# design.net
KiCad netlist of a schematic drawn in Altium Designer
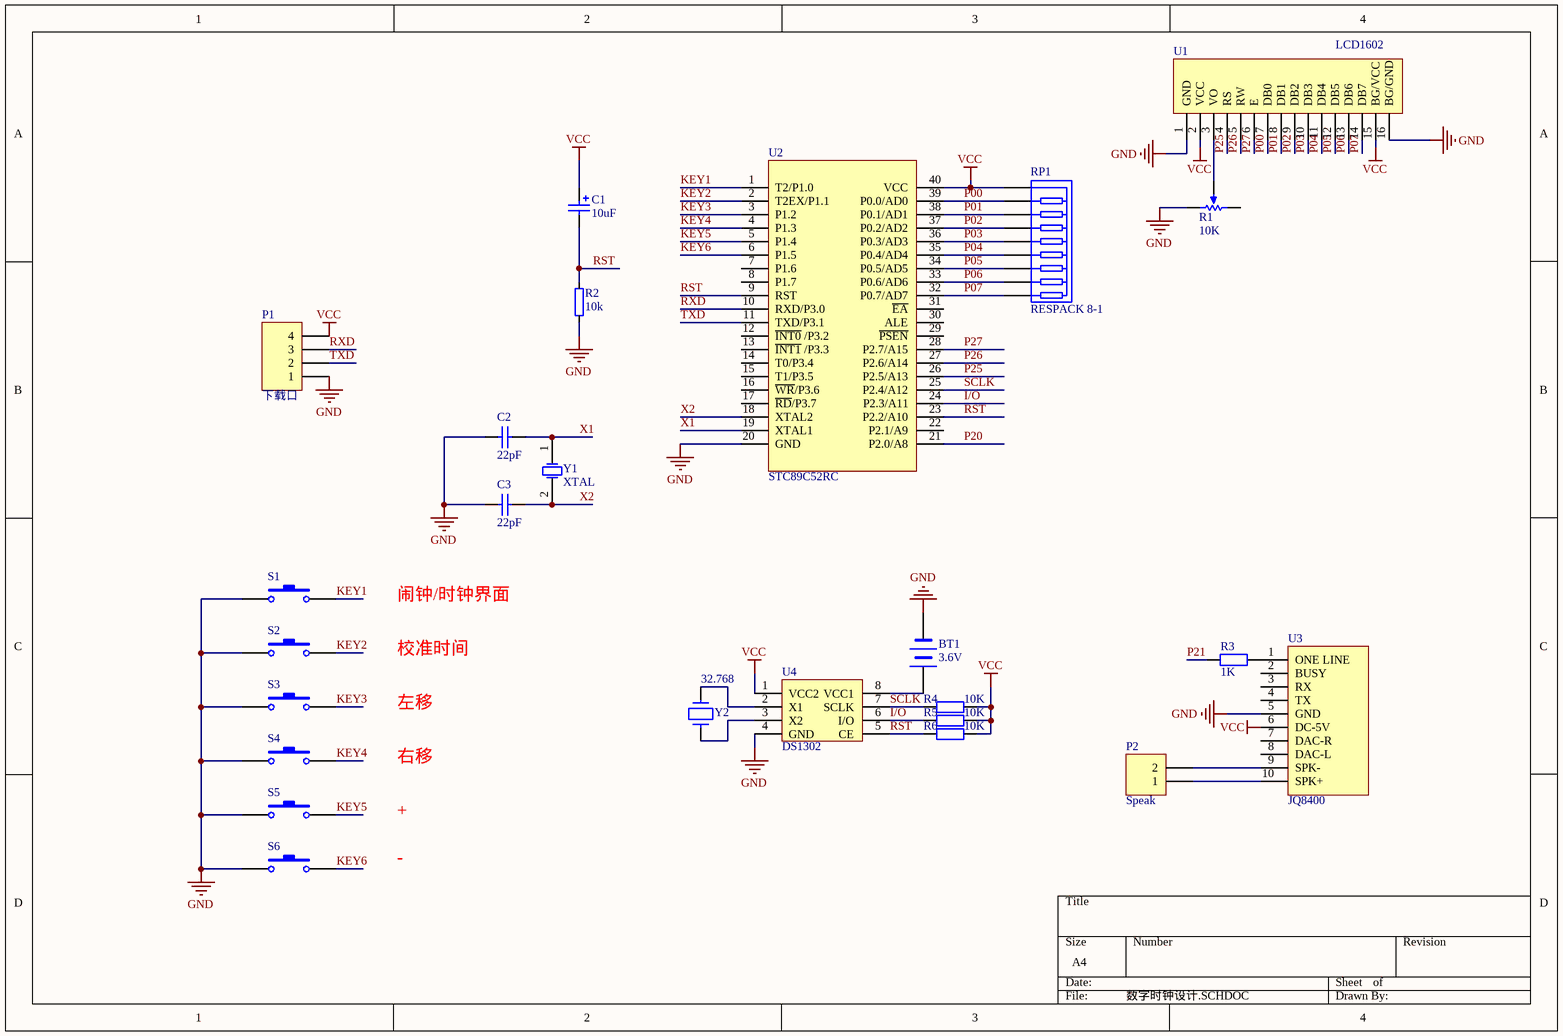
[diagram p0: 数字时钟设计.SCHDOC]

(export (version "E")
  (design (tool "Eeschema 10.0.6"))
  (components
    (comp (ref "BT1")
      (value "3.6V")
      (footprint "BT1220")
      (description "Battery")
      (libsource (lib "常用1") (part "BATTERY"))
    )
    (comp (ref "C1")
      (value "10uF")
      (footprint "1206C+")
      (description "Polarized Capacitor (Axial)")
      (fields (field (name "PUBLISHER") "Altium Limited"))
      (libsource (lib "Miscellaneous Devices") (part "Cap Pol2"))
    )
    (comp (ref "C2")
      (value "22pF")
      (footprint "0805")
      (description "Capacitor")
      (fields (field (name "Comment") "Cap") (field (name "PUBLISHER") "Altium Limited"))
      (libsource (lib "Miscellaneous Devices") (part "Cap"))
    )
    (comp (ref "C3")
      (value "22pF")
      (footprint "0805")
      (description "Capacitor")
      (fields (field (name "Comment") "Cap") (field (name "PUBLISHER") "Altium Limited"))
      (libsource (lib "Miscellaneous Devices") (part "Cap"))
    )
    (comp (ref "P1")
      (value "下载口")
      (footprint "HDR1X4")
      (description "Header, 4-Pin")
      (fields (field (name "PUBLISHER") "Altium Limited"))
      (libsource (lib "Miscellaneous Connectors") (part "Header 4"))
    )
    (comp (ref "P2")
      (value "Speak")
      (footprint "HDR1X2")
      (description "Header, 2-Pin")
      (fields (field (name "PUBLISHER") "Altium Limited"))
      (libsource (lib "Miscellaneous Connectors") (part "Header 2"))
    )
    (comp (ref "R1")
      (value "10K")
      (footprint "VR5")
      (description "Potentiometer")
      (fields (field (name "Comment") "RPot") (field (name "PUBLISHER") "Altium Limited"))
      (libsource (lib "Miscellaneous Devices") (part "RPot"))
    )
    (comp (ref "R2") (value "10k") (footprint "0805") (libsource (lib "SCHS") (part "RES5")))
    (comp (ref "R3")
      (value "1K")
      (footprint "AXIAL-0.4")
      (description "Resistor")
      (fields (field (name "Comment") "Res2") (field (name "PUBLISHER") "Altium Limited"))
      (libsource (lib "Miscellaneous Devices") (part "Res2"))
    )
    (comp (ref "R4")
      (value "10K")
      (footprint "0603r")
      (description "Resistor")
      (fields (field (name "PUBLISHER") "Altium Limited"))
      (libsource (lib "Miscellaneous Devices") (part "Res2"))
    )
    (comp (ref "R5")
      (value "10K")
      (footprint "0603r")
      (description "Resistor")
      (fields (field (name "PUBLISHER") "Altium Limited"))
      (libsource (lib "Miscellaneous Devices") (part "Res2"))
    )
    (comp (ref "R6")
      (value "10K")
      (footprint "0603r")
      (description "Resistor")
      (fields (field (name "PUBLISHER") "Altium Limited"))
      (libsource (lib "Miscellaneous Devices") (part "Res2"))
    )
    (comp (ref "RP1") (value "RESPACK 8-1") (footprint "SIP9") (libsource (lib "符号") (part "RESPACK 8-1")))
    (comp (ref "S1")
      (value "~")
      (footprint "KEY")
      (description "Switch")
      (fields (field (name "PUBLISHER") "Altium Limited"))
      (libsource (lib "Miscellaneous Devices") (part "SW-PB"))
    )
    (comp (ref "S2")
      (value "~")
      (footprint "KEY")
      (description "Switch")
      (fields (field (name "PUBLISHER") "Altium Limited"))
      (libsource (lib "Miscellaneous Devices") (part "SW-PB"))
    )
    (comp (ref "S3")
      (value "~")
      (footprint "KEY")
      (description "Switch")
      (fields (field (name "PUBLISHER") "Altium Limited"))
      (libsource (lib "Miscellaneous Devices") (part "SW-PB"))
    )
    (comp (ref "S4")
      (value "~")
      (footprint "KEY")
      (description "Switch")
      (fields (field (name "PUBLISHER") "Altium Limited"))
      (libsource (lib "Miscellaneous Devices") (part "SW-PB"))
    )
    (comp (ref "S5")
      (value "~")
      (footprint "KEY")
      (description "Switch")
      (fields (field (name "PUBLISHER") "Altium Limited"))
      (libsource (lib "Miscellaneous Devices") (part "SW-PB"))
    )
    (comp (ref "S6")
      (value "~")
      (footprint "KEY")
      (description "Switch")
      (fields (field (name "PUBLISHER") "Altium Limited"))
      (libsource (lib "Miscellaneous Devices") (part "SW-PB"))
    )
    (comp (ref "U1") (value "LCD1602") (footprint "HDR1X16") (libsource (lib "个人") (part "LCD1602")))
    (comp (ref "U2") (value "STC89C52RC") (footprint "DIP40") (libsource (lib "SCHS") (part "STC89C52RC")))
    (comp (ref "U3") (value "JQ8400") (libsource (lib "Schlib1") (part "JQ8400")))
    (comp (ref "U4") (value "DS1302") (libsource (lib "个人") (part "DS1302")))
    (comp (ref "Y1")
      (value "XTAL")
      (footprint "XTAL")
      (description "Crystal Oscillator")
      (fields (field (name "PUBLISHER") "Altium Limited"))
      (libsource (lib "Miscellaneous Devices") (part "XTAL"))
    )
    (comp (ref "Y2") (value "32.768") (footprint "XTAL_2x6") (libsource (lib "常用元件库") (part "CRYSTAL")))
  )
  (nets
    (net (code "1") (name "/I{slash}O") (class "Default")
      (node (ref "R5") (pin "1") (pinfunction "1_1") (pintype "passive"))
      (node (ref "U2") (pin "24") (pinfunction "P2.3/A11_24") (pintype "passive"))
      (node (ref "U4") (pin "6") (pinfunction "I/O_6") (pintype "passive"))
    )
    (net (code "2") (name "/KEY1") (class "Default")
      (node (ref "S1") (pin "2") (pinfunction "2_2") (pintype "passive"))
      (node (ref "U2") (pin "1") (pinfunction "T2/P1.0_1") (pintype "passive"))
    )
    (net (code "3") (name "/KEY2") (class "Default")
      (node (ref "S2") (pin "2") (pinfunction "2_2") (pintype "passive"))
      (node (ref "U2") (pin "2") (pinfunction "T2EX/P1.1_2") (pintype "passive"))
    )
    (net (code "4") (name "/KEY3") (class "Default")
      (node (ref "S3") (pin "2") (pinfunction "2_2") (pintype "passive"))
      (node (ref "U2") (pin "3") (pinfunction "P1.2_3") (pintype "passive"))
    )
    (net (code "5") (name "/KEY4") (class "Default")
      (node (ref "S4") (pin "2") (pinfunction "2_2") (pintype "passive"))
      (node (ref "U2") (pin "4") (pinfunction "P1.3_4") (pintype "passive"))
    )
    (net (code "6") (name "/KEY5") (class "Default")
      (node (ref "S5") (pin "2") (pinfunction "2_2") (pintype "passive"))
      (node (ref "U2") (pin "5") (pinfunction "P1.4_5") (pintype "passive"))
    )
    (net (code "7") (name "/KEY6") (class "Default")
      (node (ref "S6") (pin "2") (pinfunction "2_2") (pintype "passive"))
      (node (ref "U2") (pin "6") (pinfunction "P1.5_6") (pintype "passive"))
    )
    (net (code "8") (name "/P00") (class "Default")
      (node (ref "RP1") (pin "2") (pinfunction "2_2") (pintype "passive"))
      (node (ref "U1") (pin "7") (pinfunction "DB0_7") (pintype "passive"))
      (node (ref "U2") (pin "39") (pinfunction "P0.0/AD0_39") (pintype "passive"))
    )
    (net (code "9") (name "/P01") (class "Default")
      (node (ref "RP1") (pin "3") (pinfunction "3_3") (pintype "passive"))
      (node (ref "U1") (pin "8") (pinfunction "DB1_8") (pintype "passive"))
      (node (ref "U2") (pin "38") (pinfunction "P0.1/AD1_38") (pintype "passive"))
    )
    (net (code "10") (name "/P02") (class "Default")
      (node (ref "RP1") (pin "4") (pinfunction "4_4") (pintype "passive"))
      (node (ref "U1") (pin "9") (pinfunction "DB2_9") (pintype "passive"))
      (node (ref "U2") (pin "37") (pinfunction "P0.2/AD2_37") (pintype "passive"))
    )
    (net (code "11") (name "/P03") (class "Default")
      (node (ref "RP1") (pin "5") (pinfunction "5_5") (pintype "passive"))
      (node (ref "U1") (pin "10") (pinfunction "DB3_10") (pintype "passive"))
      (node (ref "U2") (pin "36") (pinfunction "P0.3/AD3_36") (pintype "passive"))
    )
    (net (code "12") (name "/P04") (class "Default")
      (node (ref "RP1") (pin "6") (pinfunction "6_6") (pintype "passive"))
      (node (ref "U1") (pin "11") (pinfunction "DB4_11") (pintype "passive"))
      (node (ref "U2") (pin "35") (pinfunction "P0.4/AD4_35") (pintype "passive"))
    )
    (net (code "13") (name "/P05") (class "Default")
      (node (ref "RP1") (pin "7") (pinfunction "7_7") (pintype "passive"))
      (node (ref "U1") (pin "12") (pinfunction "DB5_12") (pintype "passive"))
      (node (ref "U2") (pin "34") (pinfunction "P0.5/AD5_34") (pintype "passive"))
    )
    (net (code "14") (name "/P06") (class "Default")
      (node (ref "RP1") (pin "8") (pinfunction "8_8") (pintype "passive"))
      (node (ref "U1") (pin "13") (pinfunction "DB6_13") (pintype "passive"))
      (node (ref "U2") (pin "33") (pinfunction "P0.6/AD6_33") (pintype "passive"))
    )
    (net (code "15") (name "/P07") (class "Default")
      (node (ref "RP1") (pin "9") (pinfunction "9_9") (pintype "passive"))
      (node (ref "U1") (pin "14") (pinfunction "DB7_14") (pintype "passive"))
      (node (ref "U2") (pin "32") (pinfunction "P0.7/AD7_32") (pintype "passive"))
    )
    (net (code "16") (name "/P20") (class "Default")
      (node (ref "U2") (pin "21") (pinfunction "P2.0/A8_21") (pintype "passive"))
    )
    (net (code "17") (name "/P21") (class "Default")
      (node (ref "R3") (pin "1") (pinfunction "1_1") (pintype "passive"))
    )
    (net (code "18") (name "/P25") (class "Default")
      (node (ref "U1") (pin "4") (pinfunction "RS_4") (pintype "passive"))
      (node (ref "U2") (pin "26") (pinfunction "P2.5/A13_26") (pintype "passive"))
    )
    (net (code "19") (name "/P26") (class "Default")
      (node (ref "U1") (pin "5") (pinfunction "RW_5") (pintype "passive"))
      (node (ref "U2") (pin "27") (pinfunction "P2.6/A14_27") (pintype "passive"))
    )
    (net (code "20") (name "/P27") (class "Default")
      (node (ref "U1") (pin "6") (pinfunction "E_6") (pintype "passive"))
      (node (ref "U2") (pin "28") (pinfunction "P2.7/A15_28") (pintype "passive"))
    )
    (net (code "21") (name "/RST") (class "Default")
      (node (ref "C1") (pin "2") (pinfunction "2_2") (pintype "passive"))
      (node (ref "R2") (pin "2") (pintype "passive"))
      (node (ref "R6") (pin "1") (pinfunction "1_1") (pintype "passive"))
      (node (ref "U2") (pin "23") (pinfunction "P2.2/A10_23") (pintype "passive"))
      (node (ref "U2") (pin "9") (pinfunction "RST_9") (pintype "passive"))
      (node (ref "U4") (pin "5") (pinfunction "CE_5") (pintype "passive"))
    )
    (net (code "22") (name "/RXD") (class "Default")
      (node (ref "P1") (pin "3") (pinfunction "3_3") (pintype "passive"))
      (node (ref "U2") (pin "10") (pinfunction "RXD/P3.0_10") (pintype "passive"))
    )
    (net (code "23") (name "/SCLK") (class "Default")
      (node (ref "R4") (pin "1") (pinfunction "1_1") (pintype "passive"))
      (node (ref "U2") (pin "25") (pinfunction "P2.4/A12_25") (pintype "passive"))
      (node (ref "U4") (pin "7") (pinfunction "SCLK_7") (pintype "passive"))
    )
    (net (code "24") (name "/TXD") (class "Default")
      (node (ref "P1") (pin "2") (pinfunction "2_2") (pintype "passive"))
      (node (ref "U2") (pin "11") (pinfunction "TXD/P3.1_11") (pintype "passive"))
    )
    (net (code "25") (name "/X1") (class "Default")
      (node (ref "C2") (pin "2") (pinfunction "2_2") (pintype "passive"))
      (node (ref "U2") (pin "19") (pinfunction "XTAL1_19") (pintype "passive"))
      (node (ref "Y1") (pin "1") (pinfunction "OSC1_1") (pintype "passive"))
    )
    (net (code "26") (name "/X2") (class "Default")
      (node (ref "C3") (pin "2") (pinfunction "2_2") (pintype "passive"))
      (node (ref "U2") (pin "18") (pinfunction "XTAL2_18") (pintype "passive"))
      (node (ref "Y1") (pin "2") (pinfunction "OSC2_2") (pintype "passive"))
    )
    (net (code "27") (name "GND") (class "Default")
      (node (ref "BT1") (pin "2") (pinfunction "-_2") (pintype "passive"))
      (node (ref "C2") (pin "1") (pinfunction "1_1") (pintype "passive"))
      (node (ref "C3") (pin "1") (pinfunction "1_1") (pintype "passive"))
      (node (ref "P1") (pin "1") (pinfunction "1_1") (pintype "passive"))
      (node (ref "R1") (pin "2") (pinfunction "BOT_2") (pintype "passive"))
      (node (ref "R2") (pin "1") (pintype "passive"))
      (node (ref "S1") (pin "1") (pinfunction "1_1") (pintype "passive"))
      (node (ref "S2") (pin "1") (pinfunction "1_1") (pintype "passive"))
      (node (ref "S3") (pin "1") (pinfunction "1_1") (pintype "passive"))
      (node (ref "S4") (pin "1") (pinfunction "1_1") (pintype "passive"))
      (node (ref "S5") (pin "1") (pinfunction "1_1") (pintype "passive"))
      (node (ref "S6") (pin "1") (pinfunction "1_1") (pintype "passive"))
      (node (ref "U1") (pin "1") (pinfunction "GND_1") (pintype "passive"))
      (node (ref "U1") (pin "16") (pinfunction "BG/GND_16") (pintype "passive"))
      (node (ref "U2") (pin "20") (pinfunction "GND_20") (pintype "passive"))
      (node (ref "U3") (pin "5") (pinfunction "GND_5") (pintype "passive"))
      (node (ref "U4") (pin "4") (pinfunction "GND_4") (pintype "passive"))
    )
    (net (code "28") (name "Net-(BT1-+)") (class "Default")
      (node (ref "BT1") (pin "1") (pinfunction "+_1") (pintype "passive"))
      (node (ref "U4") (pin "8") (pinfunction "VCC1_8") (pintype "passive"))
    )
    (net (code "29") (name "Net-(R1-TAP)") (class "Default")
      (node (ref "R1") (pin "3") (pinfunction "TAP_3") (pintype "passive"))
      (node (ref "U1") (pin "3") (pinfunction "VO_3") (pintype "passive"))
    )
    (net (code "30") (name "Net-(U3-ONE_LINE)") (class "Default")
      (node (ref "R3") (pin "2") (pinfunction "2_2") (pintype "passive"))
      (node (ref "U3") (pin "1") (pinfunction "ONE_LINE_1") (pintype "passive"))
    )
    (net (code "31") (name "Net-(U3-SPK+)") (class "Default")
      (node (ref "P2") (pin "1") (pinfunction "1_1") (pintype "passive"))
      (node (ref "U3") (pin "10") (pinfunction "SPK+_10") (pintype "passive"))
    )
    (net (code "32") (name "Net-(U3-SPK-)") (class "Default")
      (node (ref "P2") (pin "2") (pinfunction "2_2") (pintype "passive"))
      (node (ref "U3") (pin "9") (pinfunction "SPK-_9") (pintype "passive"))
    )
    (net (code "33") (name "Net-(U4-X1)") (class "Default")
      (node (ref "U4") (pin "2") (pinfunction "X1_2") (pintype "passive"))
      (node (ref "Y2") (pin "2") (pinfunction "2_2") (pintype "passive"))
    )
    (net (code "34") (name "Net-(U4-X2)") (class "Default")
      (node (ref "U4") (pin "3") (pinfunction "X2_3") (pintype "passive"))
      (node (ref "Y2") (pin "1") (pinfunction "1_1") (pintype "passive"))
    )
    (net (code "35") (name "VCC") (class "Default")
      (node (ref "C1") (pin "1") (pinfunction "1_1") (pintype "passive"))
      (node (ref "P1") (pin "4") (pinfunction "4_4") (pintype "passive"))
      (node (ref "R4") (pin "2") (pinfunction "2_2") (pintype "passive"))
      (node (ref "R5") (pin "2") (pinfunction "2_2") (pintype "passive"))
      (node (ref "R6") (pin "2") (pinfunction "2_2") (pintype "passive"))
      (node (ref "RP1") (pin "1") (pinfunction "1_1") (pintype "passive"))
      (node (ref "U1") (pin "15") (pinfunction "BG/VCC_15") (pintype "passive"))
      (node (ref "U1") (pin "2") (pinfunction "VCC_2") (pintype "passive"))
      (node (ref "U2") (pin "40") (pinfunction "VCC_40") (pintype "passive"))
      (node (ref "U3") (pin "6") (pinfunction "DC-5V_6") (pintype "passive"))
      (node (ref "U4") (pin "1") (pinfunction "VCC2_1") (pintype "passive"))
    )
    (net (code "36") (name "unconnected-(R1-TOP-Pad1)") (class "Default")
      (node (ref "R1") (pin "1") (pinfunction "TOP_1") (pintype "passive"))
    )
    (net (code "37") (name "unconnected-(U2-ALE-Pad30)") (class "Default")
      (node (ref "U2") (pin "30") (pinfunction "ALE_30") (pintype "passive"))
    )
    (net (code "38") (name "unconnected-(U2-P1.6-Pad7)") (class "Default")
      (node (ref "U2") (pin "7") (pinfunction "P1.6_7") (pintype "passive"))
    )
    (net (code "39") (name "unconnected-(U2-P1.7-Pad8)") (class "Default")
      (node (ref "U2") (pin "8") (pinfunction "P1.7_8") (pintype "passive"))
    )
    (net (code "40") (name "unconnected-(U2-P2.1{slash}A9-Pad22)") (class "Default")
      (node (ref "U2") (pin "22") (pinfunction "P2.1/A9_22") (pintype "passive"))
    )
    (net (code "41") (name "unconnected-(U2-T0{slash}P3.4-Pad14)") (class "Default")
      (node (ref "U2") (pin "14") (pinfunction "T0/P3.4_14") (pintype "passive"))
    )
    (net (code "42") (name "unconnected-(U2-T1{slash}P3.5-Pad15)") (class "Default")
      (node (ref "U2") (pin "15") (pinfunction "T1/P3.5_15") (pintype "passive"))
    )
    (net (code "43") (name "unconnected-(U2-~{EA}-Pad31)") (class "Default")
      (node (ref "U2") (pin "31") (pinfunction "~{EA}_31") (pintype "passive"))
    )
    (net (code "44") (name "unconnected-(U2-~{INT0}_{slash}P3.2-Pad12)") (class "Default")
      (node (ref "U2") (pin "12") (pinfunction "~{INT0}_/P3.2_12") (pintype "passive"))
    )
    (net (code "45") (name "unconnected-(U2-~{INT1}_{slash}P3.3-Pad13)") (class "Default")
      (node (ref "U2") (pin "13") (pinfunction "~{INT1}_/P3.3_13") (pintype "passive"))
    )
    (net (code "46") (name "unconnected-(U2-~{PSEN}-Pad29)") (class "Default")
      (node (ref "U2") (pin "29") (pinfunction "~{PSEN}_29") (pintype "passive"))
    )
    (net (code "47") (name "unconnected-(U2-~{RD}{slash}P3.7-Pad17)") (class "Default")
      (node (ref "U2") (pin "17") (pinfunction "~{RD}/P3.7_17") (pintype "passive"))
    )
    (net (code "48") (name "unconnected-(U2-~{WR}{slash}P3.6-Pad16)") (class "Default")
      (node (ref "U2") (pin "16") (pinfunction "~{WR}/P3.6_16") (pintype "passive"))
    )
    (net (code "49") (name "unconnected-(U3-BUSY-Pad2)") (class "Default")
      (node (ref "U3") (pin "2") (pinfunction "BUSY_2") (pintype "passive"))
    )
    (net (code "50") (name "unconnected-(U3-DAC-L-Pad8)") (class "Default")
      (node (ref "U3") (pin "8") (pinfunction "DAC-L_8") (pintype "passive"))
    )
    (net (code "51") (name "unconnected-(U3-DAC-R-Pad7)") (class "Default")
      (node (ref "U3") (pin "7") (pinfunction "DAC-R_7") (pintype "passive"))
    )
    (net (code "52") (name "unconnected-(U3-RX-Pad3)") (class "Default")
      (node (ref "U3") (pin "3") (pinfunction "RX_3") (pintype "passive"))
    )
    (net (code "53") (name "unconnected-(U3-TX-Pad4)") (class "Default")
      (node (ref "U3") (pin "4") (pinfunction "TX_4") (pintype "passive"))
    )
  )
)
